# LBF_Op-Amp_Gain.net
KiCad netlist of a schematic drawn in Altium Designer
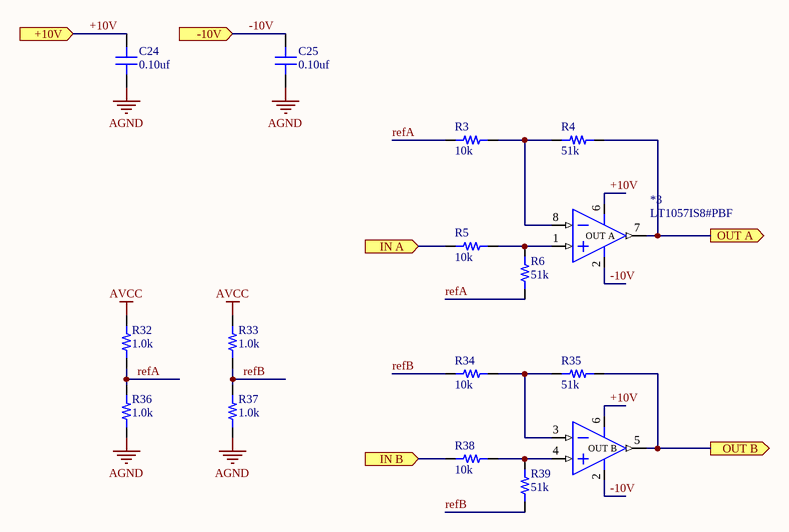
[diagram p0: LBF Op-Amp Gain.SchDoc]

(export (version "E")
  (design (tool "Eeschema 10.0.6"))
  (components
    (comp (ref "*3")
      (value "LT1057IS8#PBF")
      (footprint "SOIC-8")
      (description "IC OPAMP JFET 5MHZ 8SO")
      (fields (field (name "CREATED_BY") "Albert Panuco"))
      (libsource (lib "Altium-Lib") (part "LT1057IS8#PBF"))
    )
    (comp (ref "C24")
      (value "0.10uf")
      (footprint "CAP 0805/2012")
      (fields
        (field (name "Comment") "Capacitor MLCC 0.10uf 25V CAP 0805/2012")
        (field (name "CREATED_BY") "Nick Mah")
      )
      (libsource (lib "Altium-Lib") (part "Capacitor"))
    )
    (comp (ref "C25")
      (value "0.10uf")
      (footprint "CAP 0805/2012")
      (fields
        (field (name "Comment") "Capacitor MLCC 0.10uf 25V CAP 0805/2012")
        (field (name "CREATED_BY") "Nick Mah")
      )
      (libsource (lib "Altium-Lib") (part "Capacitor"))
    )
    (comp (ref "R3")
      (value "10k")
      (footprint "RES 0805/2012")
      (fields
        (field (name "TOLERANCE") "1%")
        (field (name "POWER") "1/10W")
        (field (name "Comment") "Resistor 10k 0805 1/10W 1%")
        (field (name "CREATED_BY") "Nick Mah")
      )
      (libsource (lib "Altium-Lib") (part "Resistor"))
    )
    (comp (ref "R4")
      (value "51k")
      (footprint "RES 0805/2012")
      (fields
        (field (name "TOLERANCE") "1%")
        (field (name "POWER") "1/10W")
        (field (name "Comment") "Resistor 51k 0805 1/10W 1%")
        (field (name "CREATED_BY") "Nick Mah")
      )
      (libsource (lib "Altium-Lib") (part "Resistor"))
    )
    (comp (ref "R5")
      (value "10k")
      (footprint "RES 0805/2012")
      (fields
        (field (name "TOLERANCE") "1%")
        (field (name "POWER") "1/10W")
        (field (name "Comment") "Resistor 10k 0805 1/10W 1%")
        (field (name "CREATED_BY") "Nick Mah")
      )
      (libsource (lib "Altium-Lib") (part "Resistor"))
    )
    (comp (ref "R6")
      (value "51k")
      (footprint "RES 0805/2012")
      (fields
        (field (name "TOLERANCE") "1%")
        (field (name "POWER") "1/10W")
        (field (name "Comment") "Resistor 51k 0805 1/10W 1%")
        (field (name "CREATED_BY") "Nick Mah")
      )
      (libsource (lib "Altium-Lib") (part "Resistor"))
    )
    (comp (ref "R32")
      (value "1.0k")
      (footprint "RES 0805/2012")
      (fields
        (field (name "TOLERANCE") "1%")
        (field (name "POWER") "1/10W")
        (field (name "Comment") "Resistor 1.0k 0805 1/10W 1%")
        (field (name "CREATED_BY") "Nick Mah")
      )
      (libsource (lib "Altium-Lib") (part "Resistor"))
    )
    (comp (ref "R33")
      (value "1.0k")
      (footprint "RES 0805/2012")
      (fields
        (field (name "TOLERANCE") "1%")
        (field (name "POWER") "1/10W")
        (field (name "Comment") "Resistor 1.0k 0805 1/10W 1%")
        (field (name "CREATED_BY") "Nick Mah")
      )
      (libsource (lib "Altium-Lib") (part "Resistor"))
    )
    (comp (ref "R34")
      (value "10k")
      (footprint "RES 0805/2012")
      (fields
        (field (name "TOLERANCE") "1%")
        (field (name "POWER") "1/10W")
        (field (name "Comment") "Resistor 10k 0805 1/10W 1%")
        (field (name "CREATED_BY") "Nick Mah")
      )
      (libsource (lib "Altium-Lib") (part "Resistor"))
    )
    (comp (ref "R35")
      (value "51k")
      (footprint "RES 0805/2012")
      (fields
        (field (name "TOLERANCE") "1%")
        (field (name "POWER") "1/10W")
        (field (name "Comment") "Resistor 51k 0805 1/10W 1%")
        (field (name "CREATED_BY") "Nick Mah")
      )
      (libsource (lib "Altium-Lib") (part "Resistor"))
    )
    (comp (ref "R36")
      (value "1.0k")
      (footprint "RES 0805/2012")
      (fields
        (field (name "TOLERANCE") "1%")
        (field (name "POWER") "1/10W")
        (field (name "Comment") "Resistor 1.0k 0805 1/10W 1%")
        (field (name "CREATED_BY") "Nick Mah")
      )
      (libsource (lib "Altium-Lib") (part "Resistor"))
    )
    (comp (ref "R37")
      (value "1.0k")
      (footprint "RES 0805/2012")
      (fields
        (field (name "TOLERANCE") "1%")
        (field (name "POWER") "1/10W")
        (field (name "Comment") "Resistor 1.0k 0805 1/10W 1%")
        (field (name "CREATED_BY") "Nick Mah")
      )
      (libsource (lib "Altium-Lib") (part "Resistor"))
    )
    (comp (ref "R38")
      (value "10k")
      (footprint "RES 0805/2012")
      (fields
        (field (name "TOLERANCE") "1%")
        (field (name "POWER") "1/10W")
        (field (name "Comment") "Resistor 10k 0805 1/10W 1%")
        (field (name "CREATED_BY") "Nick Mah")
      )
      (libsource (lib "Altium-Lib") (part "Resistor"))
    )
    (comp (ref "R39")
      (value "51k")
      (footprint "RES 0805/2012")
      (fields
        (field (name "TOLERANCE") "1%")
        (field (name "POWER") "1/10W")
        (field (name "Comment") "Resistor 51k 0805 1/10W 1%")
        (field (name "CREATED_BY") "Nick Mah")
      )
      (libsource (lib "Altium-Lib") (part "Resistor"))
    )
  )
  (nets
    (net (code "1") (name "/+10V") (class "Default")
      (node (ref "*3") (pin "6") (pinfunction "+Vcc_6") (pintype "input"))
      (node (ref "C24") (pin "2") (pinfunction "2_2") (pintype "passive"))
    )
    (net (code "2") (name "/-10V") (class "Default")
      (node (ref "*3") (pin "2") (pinfunction "-Vcc_2") (pintype "input"))
      (node (ref "C25") (pin "2") (pinfunction "2_2") (pintype "passive"))
    )
    (net (code "3") (name "/IN A") (class "Default")
      (node (ref "R5") (pin "1") (pinfunction "1_1") (pintype "passive"))
    )
    (net (code "4") (name "/IN B") (class "Default")
      (node (ref "R38") (pin "1") (pinfunction "1_1") (pintype "passive"))
    )
    (net (code "5") (name "/OUT A") (class "Default")
      (node (ref "*3") (pin "7") (pinfunction "OUT_A_7") (pintype "output"))
      (node (ref "R4") (pin "2") (pinfunction "2_2") (pintype "passive"))
    )
    (net (code "6") (name "/OUT B") (class "Default")
      (node (ref "*3") (pin "5") (pinfunction "OUT_B_5") (pintype "output"))
      (node (ref "R35") (pin "2") (pinfunction "2_2") (pintype "passive"))
    )
    (net (code "7") (name "/refA") (class "Default")
      (node (ref "R3") (pin "1") (pinfunction "1_1") (pintype "passive"))
      (node (ref "R32") (pin "1") (pinfunction "1_1") (pintype "passive"))
      (node (ref "R36") (pin "2") (pinfunction "2_2") (pintype "passive"))
      (node (ref "R6") (pin "2") (pinfunction "2_2") (pintype "passive"))
    )
    (net (code "8") (name "/refB") (class "Default")
      (node (ref "R33") (pin "1") (pinfunction "1_1") (pintype "passive"))
      (node (ref "R34") (pin "1") (pinfunction "1_1") (pintype "passive"))
      (node (ref "R37") (pin "2") (pinfunction "2_2") (pintype "passive"))
      (node (ref "R39") (pin "2") (pinfunction "2_2") (pintype "passive"))
    )
    (net (code "9") (name "AGND") (class "Default")
      (node (ref "C24") (pin "1") (pinfunction "1_1") (pintype "passive"))
      (node (ref "C25") (pin "1") (pinfunction "1_1") (pintype "passive"))
      (node (ref "R36") (pin "1") (pinfunction "1_1") (pintype "passive"))
      (node (ref "R37") (pin "1") (pinfunction "1_1") (pintype "passive"))
    )
    (net (code "10") (name "AVCC") (class "Default")
      (node (ref "R32") (pin "2") (pinfunction "2_2") (pintype "passive"))
      (node (ref "R33") (pin "2") (pinfunction "2_2") (pintype "passive"))
    )
    (net (code "11") (name "Net-(*3-+IN_A)") (class "Default")
      (node (ref "*3") (pin "1") (pinfunction "+IN_A_1") (pintype "input"))
      (node (ref "R5") (pin "2") (pinfunction "2_2") (pintype "passive"))
      (node (ref "R6") (pin "1") (pinfunction "1_1") (pintype "passive"))
    )
    (net (code "12") (name "Net-(*3-+IN_B-Pad3)") (class "Default")
      (node (ref "*3") (pin "3") (pinfunction "+IN_B_3") (pintype "input"))
      (node (ref "R34") (pin "2") (pinfunction "2_2") (pintype "passive"))
      (node (ref "R35") (pin "1") (pinfunction "1_1") (pintype "passive"))
    )
    (net (code "13") (name "Net-(*3-+IN_B-Pad4)") (class "Default")
      (node (ref "*3") (pin "4") (pinfunction "+IN_B_4") (pintype "input"))
      (node (ref "R38") (pin "2") (pinfunction "2_2") (pintype "passive"))
      (node (ref "R39") (pin "1") (pinfunction "1_1") (pintype "passive"))
    )
    (net (code "14") (name "Net-(*3--IN_A)") (class "Default")
      (node (ref "*3") (pin "8") (pinfunction "-IN_A_8") (pintype "input"))
      (node (ref "R3") (pin "2") (pinfunction "2_2") (pintype "passive"))
      (node (ref "R4") (pin "1") (pinfunction "1_1") (pintype "passive"))
    )
  )
)
